# BTT_Manta_M5P_Julia_Daughter_Board.net
KiCad netlist of a schematic drawn in EAGLE
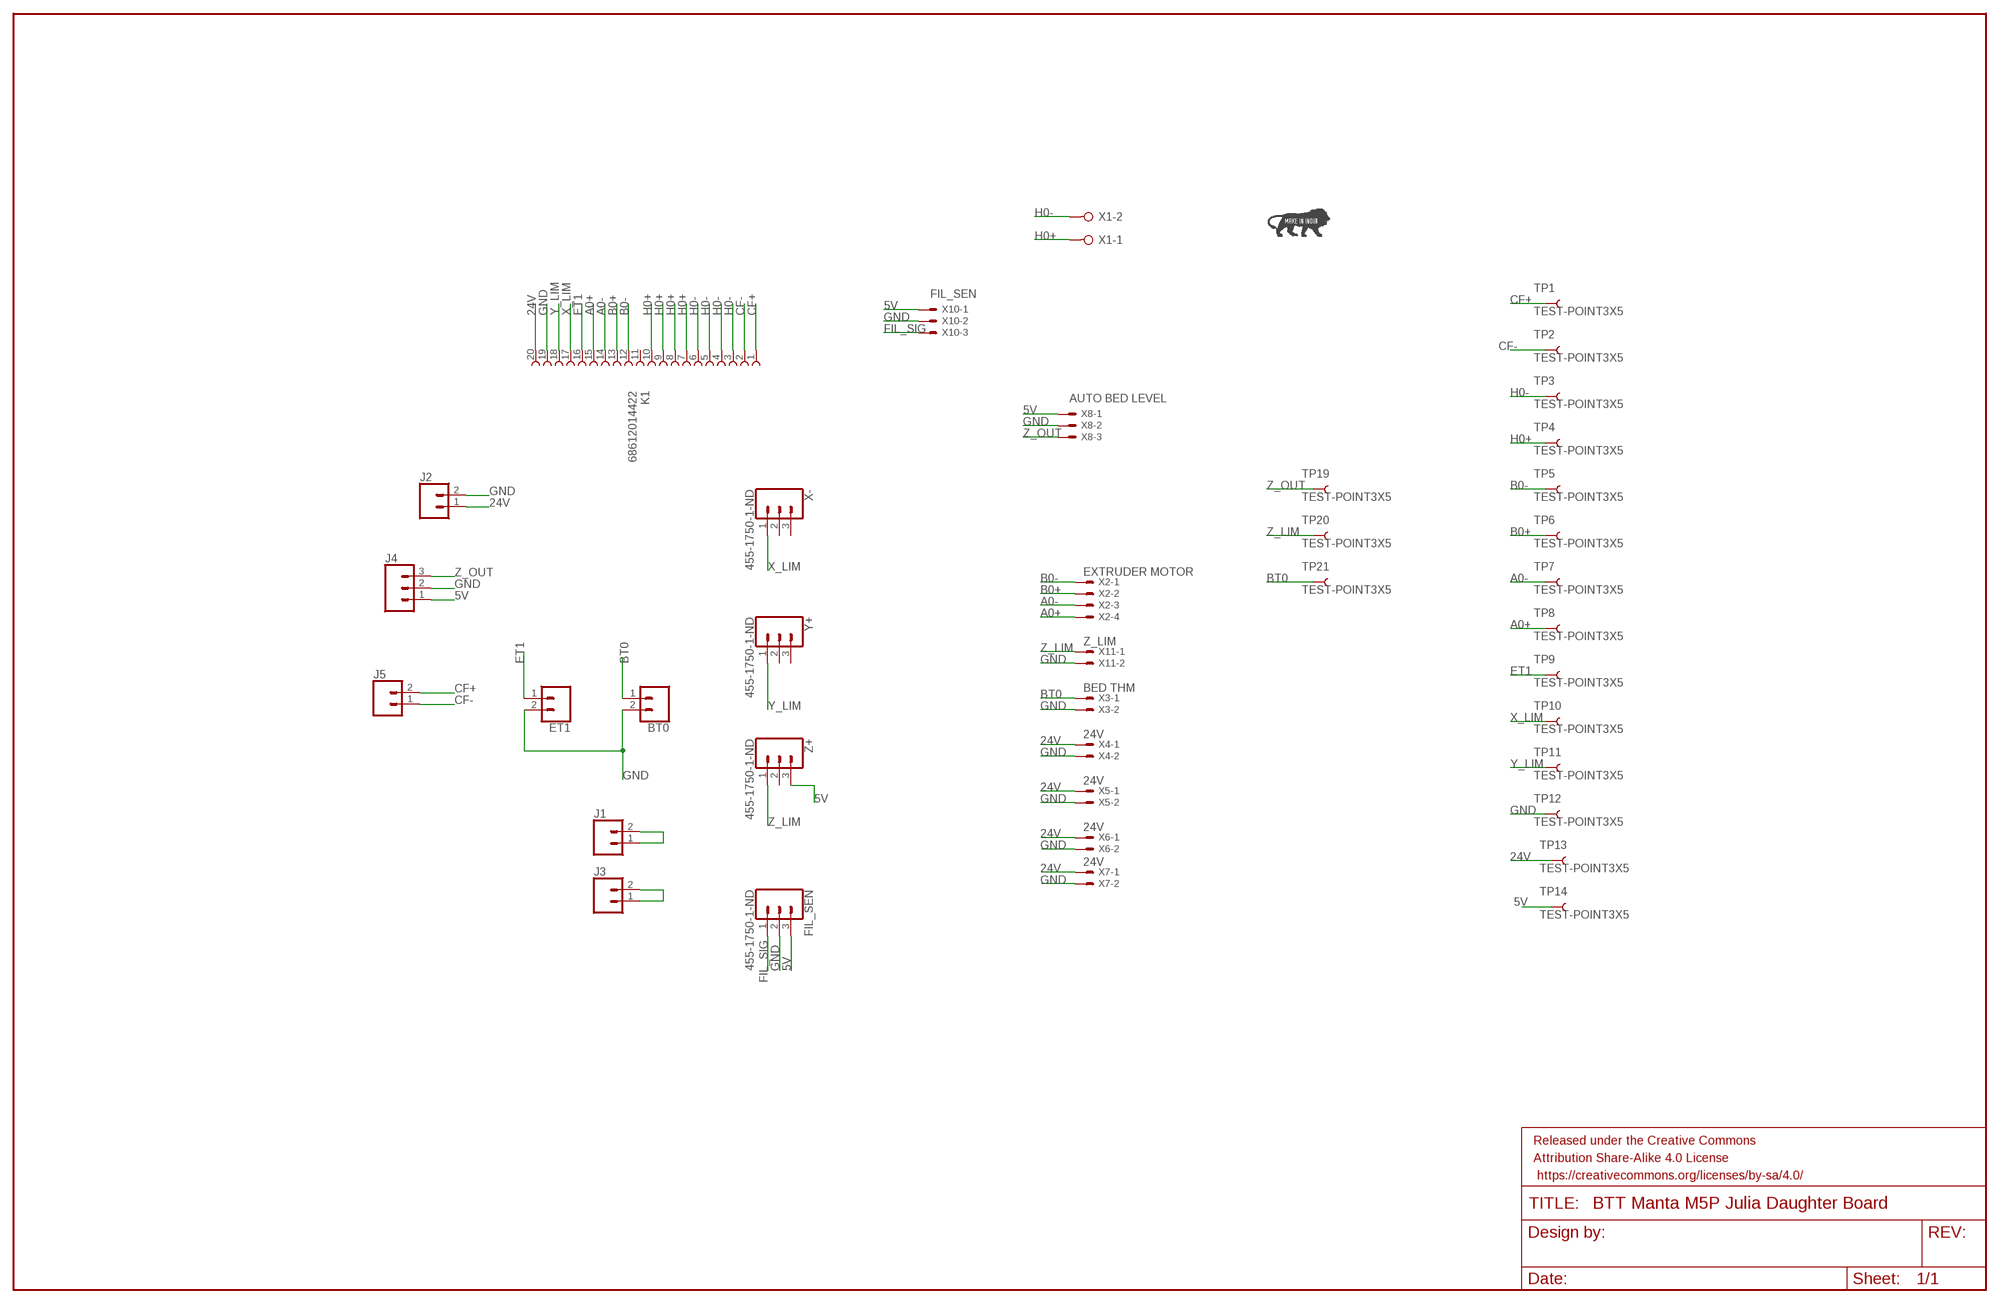
[diagram p0: schematic, sheet 1]

(export (version "E")
  (design (tool "Eeschema 10.0.6"))
  (components
    (comp (ref "BT0")
      (value "CONN_02")
      (footprint "eagle-import:1X02")
      (libsource (lib "eagle-import") (part "CONN_02"))
    )
    (comp (ref "ET1")
      (value "CONN_02")
      (footprint "eagle-import:1X02")
      (libsource (lib "eagle-import") (part "CONN_02"))
    )
    (comp (ref "FIL_SEN")
      (value "455-1750-1-ND")
      (footprint "eagle-import:1X03")
      (libsource (lib "eagle-import") (part "CONN_03"))
    )
    (comp (ref "FRAME1")
      (value "FRAME-LEDGER")
      (footprint "eagle-import:CREATIVE_COMMONS")
      (libsource (lib "eagle-import") (part "FRAME-LEDGER"))
    )
    (comp (ref "J1")
      (value "CONN_02")
      (footprint "eagle-import:1X02")
      (libsource (lib "eagle-import") (part "SparkFun-Connectors_513_CONN_02"))
    )
    (comp (ref "J2")
      (value "CONN_02")
      (footprint "eagle-import:1X02")
      (libsource (lib "eagle-import") (part "SparkFun-Connectors_513_CONN_02"))
    )
    (comp (ref "J3")
      (value "CONN_02")
      (footprint "eagle-import:1X02")
      (libsource (lib "eagle-import") (part "SparkFun-Connectors_513_CONN_02"))
    )
    (comp (ref "J4")
      (value "CONN_03")
      (footprint "eagle-import:1X03")
      (libsource (lib "eagle-import") (part "SparkFun-Connectors_513_CONN_03"))
    )
    (comp (ref "J5")
      (value "CONN_02")
      (footprint "eagle-import:1X02")
      (libsource (lib "eagle-import") (part "SparkFun-Connectors_513_CONN_02"))
    )
    (comp (ref "K1")
      (value "68612014422")
      (footprint "eagle-import:68612014422")
      (libsource (lib "eagle-import") (part "68612014422"))
    )
    (comp (ref "TP1")
      (value "TEST-POINT3X5")
      (footprint "eagle-import:PAD.03X.05")
      (libsource (lib "eagle-import") (part "TEST-POINT3X5"))
    )
    (comp (ref "TP2")
      (value "TEST-POINT3X5")
      (footprint "eagle-import:PAD.03X.05")
      (libsource (lib "eagle-import") (part "TEST-POINT3X5"))
    )
    (comp (ref "TP3")
      (value "TEST-POINT3X5")
      (footprint "eagle-import:PAD.03X.05")
      (libsource (lib "eagle-import") (part "TEST-POINT3X5"))
    )
    (comp (ref "TP4")
      (value "TEST-POINT3X5")
      (footprint "eagle-import:PAD.03X.05")
      (libsource (lib "eagle-import") (part "TEST-POINT3X5"))
    )
    (comp (ref "TP5")
      (value "TEST-POINT3X5")
      (footprint "eagle-import:PAD.03X.05")
      (libsource (lib "eagle-import") (part "TEST-POINT3X5"))
    )
    (comp (ref "TP6")
      (value "TEST-POINT3X5")
      (footprint "eagle-import:PAD.03X.05")
      (libsource (lib "eagle-import") (part "TEST-POINT3X5"))
    )
    (comp (ref "TP7")
      (value "TEST-POINT3X5")
      (footprint "eagle-import:PAD.03X.05")
      (libsource (lib "eagle-import") (part "TEST-POINT3X5"))
    )
    (comp (ref "TP8")
      (value "TEST-POINT3X5")
      (footprint "eagle-import:PAD.03X.05")
      (libsource (lib "eagle-import") (part "TEST-POINT3X5"))
    )
    (comp (ref "TP9")
      (value "TEST-POINT3X5")
      (footprint "eagle-import:PAD.03X.05")
      (libsource (lib "eagle-import") (part "TEST-POINT3X5"))
    )
    (comp (ref "TP10")
      (value "TEST-POINT3X5")
      (footprint "eagle-import:PAD.03X.05")
      (libsource (lib "eagle-import") (part "TEST-POINT3X5"))
    )
    (comp (ref "TP11")
      (value "TEST-POINT3X5")
      (footprint "eagle-import:PAD.03X.05")
      (libsource (lib "eagle-import") (part "TEST-POINT3X5"))
    )
    (comp (ref "TP12")
      (value "TEST-POINT3X5")
      (footprint "eagle-import:PAD.03X.05")
      (libsource (lib "eagle-import") (part "TEST-POINT3X5"))
    )
    (comp (ref "TP13")
      (value "TEST-POINT3X5")
      (footprint "eagle-import:PAD.03X.05")
      (libsource (lib "eagle-import") (part "TEST-POINT3X5"))
    )
    (comp (ref "TP14")
      (value "TEST-POINT3X5")
      (footprint "eagle-import:PAD.03X.05")
      (libsource (lib "eagle-import") (part "TEST-POINT3X5"))
    )
    (comp (ref "TP19")
      (value "TEST-POINT3X5")
      (footprint "eagle-import:PAD.03X.05")
      (libsource (lib "eagle-import") (part "TEST-POINT3X5"))
    )
    (comp (ref "TP20")
      (value "TEST-POINT3X5")
      (footprint "eagle-import:PAD.03X.05")
      (libsource (lib "eagle-import") (part "TEST-POINT3X5"))
    )
    (comp (ref "TP21")
      (value "TEST-POINT3X5")
      (footprint "eagle-import:PAD.03X.05")
      (libsource (lib "eagle-import") (part "TEST-POINT3X5"))
    )
    (comp (ref "U$2")
      (value "MAKEININDIA")
      (footprint "eagle-import:MAKEININDIA")
      (libsource (lib "eagle-import") (part "MAKEININDIA"))
    )
    (comp (ref "X-")
      (value "455-1750-1-ND")
      (footprint "eagle-import:1X03")
      (libsource (lib "eagle-import") (part "CONN_03"))
    )
    (comp (ref "X1")
      (value "W237-02P")
      (footprint "eagle-import:W237-132")
      (libsource (lib "eagle-import") (part "W237-02P"))
    )
    (comp (ref "X2")
      (value "EXTRUDER MOTOR")
      (footprint "eagle-import:JST-XH-04-PACKAGE-LONG-PAD")
      (libsource (lib "eagle-import") (part "JST-XH-04-PIN-LONG-PAD"))
    )
    (comp (ref "X3")
      (value "BED THM")
      (footprint "eagle-import:JST-XH-02-PACKAGE-LONG-PAD")
      (libsource (lib "eagle-import") (part "JST-XH-02-PIN-LONG-PAD"))
    )
    (comp (ref "X4")
      (value "24V")
      (footprint "eagle-import:JST-XH-02-PACKAGE-LONG-PAD")
      (libsource (lib "eagle-import") (part "JST-XH-02-PIN-LONG-PAD"))
    )
    (comp (ref "X5")
      (value "24V")
      (footprint "eagle-import:JST-XH-02-PACKAGE-LONG-PAD")
      (libsource (lib "eagle-import") (part "JST-XH-02-PIN-LONG-PAD"))
    )
    (comp (ref "X6")
      (value "24V")
      (footprint "eagle-import:JST-XH-02-PACKAGE-LONG-PAD")
      (libsource (lib "eagle-import") (part "JST-XH-02-PIN-LONG-PAD"))
    )
    (comp (ref "X7")
      (value "24V")
      (footprint "eagle-import:JST-XH-02-PACKAGE-LONG-PAD")
      (libsource (lib "eagle-import") (part "JST-XH-02-PIN-LONG-PAD"))
    )
    (comp (ref "X8")
      (value "JST-XH-03-PIN-LONG-PAD")
      (footprint "eagle-import:JST-XH-03-PACKAGE-LONG-PAD")
      (fields (field (name "VALUE1") "AUTO BED LEVEL"))
      (libsource (lib "eagle-import") (part "JST-XH-03-PIN-LONG-PAD"))
    )
    (comp (ref "X10")
      (value "JST-XH-03-PIN-LONG-PAD")
      (footprint "eagle-import:JST-XH-03-PACKAGE-LONG-PAD")
      (fields (field (name "VALUE1") "FIL_SEN"))
      (libsource (lib "eagle-import") (part "JST-XH-03-PIN-LONG-PAD"))
    )
    (comp (ref "X11")
      (value "Z_LIM")
      (footprint "eagle-import:JST-XH-02-PACKAGE-LONG-PAD")
      (libsource (lib "eagle-import") (part "JST-XH-02-PIN-LONG-PAD"))
    )
    (comp (ref "Y+")
      (value "455-1750-1-ND")
      (footprint "eagle-import:1X03")
      (libsource (lib "eagle-import") (part "CONN_03"))
    )
    (comp (ref "Z+")
      (value "455-1750-1-ND")
      (footprint "eagle-import:1X03")
      (libsource (lib "eagle-import") (part "CONN_03"))
    )
  )
  (nets
    (net (code "1") (name "/5V") (class "Default")
      (node (ref "FIL_SEN") (pin "3") (pinfunction "3_3") (pintype "passive"))
      (node (ref "J4") (pin "1") (pinfunction "1_1") (pintype "passive"))
      (node (ref "TP14") (pin "P$1") (pinfunction "1_P$1") (pintype "bidirectional"))
      (node (ref "X10") (pin "1") (pinfunction "S_1") (pintype "passive"))
      (node (ref "X8") (pin "1") (pinfunction "S_1") (pintype "passive"))
      (node (ref "Z+") (pin "3") (pinfunction "3_3") (pintype "passive"))
    )
    (net (code "2") (name "/24V") (class "Default")
      (node (ref "J2") (pin "1") (pinfunction "1_1") (pintype "passive"))
      (node (ref "K1") (pin "20") (pinfunction "20_20") (pintype "passive"))
      (node (ref "TP13") (pin "P$1") (pinfunction "1_P$1") (pintype "bidirectional"))
      (node (ref "X4") (pin "1") (pinfunction "S_1") (pintype "passive"))
      (node (ref "X5") (pin "1") (pinfunction "S_1") (pintype "passive"))
      (node (ref "X6") (pin "1") (pinfunction "S_1") (pintype "passive"))
      (node (ref "X7") (pin "1") (pinfunction "S_1") (pintype "passive"))
    )
    (net (code "3") (name "/A0+") (class "Default")
      (node (ref "K1") (pin "15") (pinfunction "15_15") (pintype "passive"))
      (node (ref "TP8") (pin "P$1") (pinfunction "1_P$1") (pintype "bidirectional"))
      (node (ref "X2") (pin "4") (pinfunction "S_4") (pintype "passive"))
    )
    (net (code "4") (name "/A0-") (class "Default")
      (node (ref "K1") (pin "14") (pinfunction "14_14") (pintype "passive"))
      (node (ref "TP7") (pin "P$1") (pinfunction "1_P$1") (pintype "bidirectional"))
      (node (ref "X2") (pin "3") (pinfunction "S_3") (pintype "passive"))
    )
    (net (code "5") (name "/B0+") (class "Default")
      (node (ref "K1") (pin "13") (pinfunction "13_13") (pintype "passive"))
      (node (ref "TP6") (pin "P$1") (pinfunction "1_P$1") (pintype "bidirectional"))
      (node (ref "X2") (pin "2") (pinfunction "S_2") (pintype "passive"))
    )
    (net (code "6") (name "/B0-") (class "Default")
      (node (ref "K1") (pin "12") (pinfunction "12_12") (pintype "passive"))
      (node (ref "TP5") (pin "P$1") (pinfunction "1_P$1") (pintype "bidirectional"))
      (node (ref "X2") (pin "1") (pinfunction "S_1") (pintype "passive"))
    )
    (net (code "7") (name "/BT0") (class "Default")
      (node (ref "BT0") (pin "1") (pinfunction "1_1") (pintype "passive"))
      (node (ref "TP21") (pin "P$1") (pinfunction "1_P$1") (pintype "bidirectional"))
      (node (ref "X3") (pin "1") (pinfunction "S_1") (pintype "passive"))
    )
    (net (code "8") (name "/CF+") (class "Default")
      (node (ref "J5") (pin "2") (pinfunction "2_2") (pintype "passive"))
      (node (ref "K1") (pin "1") (pinfunction "1_1") (pintype "passive"))
      (node (ref "TP1") (pin "P$1") (pinfunction "1_P$1") (pintype "bidirectional"))
    )
    (net (code "9") (name "/CF-") (class "Default")
      (node (ref "J5") (pin "1") (pinfunction "1_1") (pintype "passive"))
      (node (ref "K1") (pin "2") (pinfunction "2_2") (pintype "passive"))
      (node (ref "TP2") (pin "P$1") (pinfunction "1_P$1") (pintype "bidirectional"))
    )
    (net (code "10") (name "/ET1") (class "Default")
      (node (ref "ET1") (pin "1") (pinfunction "1_1") (pintype "passive"))
      (node (ref "K1") (pin "16") (pinfunction "16_16") (pintype "passive"))
      (node (ref "TP9") (pin "P$1") (pinfunction "1_P$1") (pintype "bidirectional"))
    )
    (net (code "11") (name "/FIL_SIG") (class "Default")
      (node (ref "FIL_SEN") (pin "1") (pinfunction "1_1") (pintype "passive"))
      (node (ref "X10") (pin "3") (pinfunction "S_3") (pintype "passive"))
    )
    (net (code "12") (name "/GND") (class "Default")
      (node (ref "BT0") (pin "2") (pinfunction "2_2") (pintype "passive"))
      (node (ref "ET1") (pin "2") (pinfunction "2_2") (pintype "passive"))
      (node (ref "FIL_SEN") (pin "2") (pinfunction "2_2") (pintype "passive"))
      (node (ref "J2") (pin "2") (pinfunction "2_2") (pintype "passive"))
      (node (ref "J4") (pin "2") (pinfunction "2_2") (pintype "passive"))
      (node (ref "K1") (pin "19") (pinfunction "19_19") (pintype "passive"))
      (node (ref "TP12") (pin "P$1") (pinfunction "1_P$1") (pintype "bidirectional"))
      (node (ref "X10") (pin "2") (pinfunction "S_2") (pintype "passive"))
      (node (ref "X11") (pin "2") (pinfunction "S_2") (pintype "passive"))
      (node (ref "X3") (pin "2") (pinfunction "S_2") (pintype "passive"))
      (node (ref "X4") (pin "2") (pinfunction "S_2") (pintype "passive"))
      (node (ref "X5") (pin "2") (pinfunction "S_2") (pintype "passive"))
      (node (ref "X6") (pin "2") (pinfunction "S_2") (pintype "passive"))
      (node (ref "X7") (pin "2") (pinfunction "S_2") (pintype "passive"))
      (node (ref "X8") (pin "2") (pinfunction "S_2") (pintype "passive"))
    )
    (net (code "13") (name "/H0+") (class "Default")
      (node (ref "K1") (pin "10") (pinfunction "10_10") (pintype "passive"))
      (node (ref "K1") (pin "7") (pinfunction "7_7") (pintype "passive"))
      (node (ref "K1") (pin "8") (pinfunction "8_8") (pintype "passive"))
      (node (ref "K1") (pin "9") (pinfunction "9_9") (pintype "passive"))
      (node (ref "TP4") (pin "P$1") (pinfunction "1_P$1") (pintype "bidirectional"))
      (node (ref "X1") (pin "1") (pinfunction "KL_1") (pintype "passive"))
    )
    (net (code "14") (name "/H0-") (class "Default")
      (node (ref "K1") (pin "3") (pinfunction "3_3") (pintype "passive"))
      (node (ref "K1") (pin "4") (pinfunction "4_4") (pintype "passive"))
      (node (ref "K1") (pin "5") (pinfunction "5_5") (pintype "passive"))
      (node (ref "K1") (pin "6") (pinfunction "6_6") (pintype "passive"))
      (node (ref "TP3") (pin "P$1") (pinfunction "1_P$1") (pintype "bidirectional"))
      (node (ref "X1") (pin "2") (pinfunction "KL_2") (pintype "passive"))
    )
    (net (code "15") (name "/X_LIM") (class "Default")
      (node (ref "K1") (pin "17") (pinfunction "17_17") (pintype "passive"))
      (node (ref "TP10") (pin "P$1") (pinfunction "1_P$1") (pintype "bidirectional"))
      (node (ref "X-") (pin "1") (pinfunction "1_1") (pintype "passive"))
    )
    (net (code "16") (name "/Y_LIM") (class "Default")
      (node (ref "K1") (pin "18") (pinfunction "18_18") (pintype "passive"))
      (node (ref "TP11") (pin "P$1") (pinfunction "1_P$1") (pintype "bidirectional"))
      (node (ref "Y+") (pin "1") (pinfunction "1_1") (pintype "passive"))
    )
    (net (code "17") (name "/Z_LIM") (class "Default")
      (node (ref "TP20") (pin "P$1") (pinfunction "1_P$1") (pintype "bidirectional"))
      (node (ref "X11") (pin "1") (pinfunction "S_1") (pintype "passive"))
      (node (ref "Z+") (pin "1") (pinfunction "1_1") (pintype "passive"))
    )
    (net (code "18") (name "/Z_OUT") (class "Default")
      (node (ref "J4") (pin "3") (pinfunction "3_3") (pintype "passive"))
      (node (ref "TP19") (pin "P$1") (pinfunction "1_P$1") (pintype "bidirectional"))
      (node (ref "X8") (pin "3") (pinfunction "S_3") (pintype "passive"))
    )
    (net (code "19") (name "Net-(J1-Pad1)") (class "Default")
      (node (ref "J1") (pin "1") (pinfunction "1_1") (pintype "passive"))
      (node (ref "J1") (pin "2") (pinfunction "2_2") (pintype "passive"))
    )
    (net (code "20") (name "Net-(J3-Pad1)") (class "Default")
      (node (ref "J3") (pin "1") (pinfunction "1_1") (pintype "passive"))
      (node (ref "J3") (pin "2") (pinfunction "2_2") (pintype "passive"))
    )
    (net (code "21") (name "unconnected-(K1-Pad11)") (class "Default")
      (node (ref "K1") (pin "11") (pinfunction "11_11") (pintype "passive"))
    )
    (net (code "22") (name "unconnected-(X--Pad2)") (class "Default")
      (node (ref "X-") (pin "2") (pinfunction "2_2") (pintype "passive"))
    )
    (net (code "23") (name "unconnected-(X--Pad3)") (class "Default")
      (node (ref "X-") (pin "3") (pinfunction "3_3") (pintype "passive"))
    )
    (net (code "24") (name "unconnected-(Y+-Pad2)") (class "Default")
      (node (ref "Y+") (pin "2") (pinfunction "2_2") (pintype "passive"))
    )
    (net (code "25") (name "unconnected-(Y+-Pad3)") (class "Default")
      (node (ref "Y+") (pin "3") (pinfunction "3_3") (pintype "passive"))
    )
    (net (code "26") (name "unconnected-(Z+-Pad2)") (class "Default")
      (node (ref "Z+") (pin "2") (pinfunction "2_2") (pintype "passive"))
    )
  )
)
